# LB_BIT_o3_RGBLED-v02_rev1.net
KiCad netlist of a schematic drawn in EAGLE
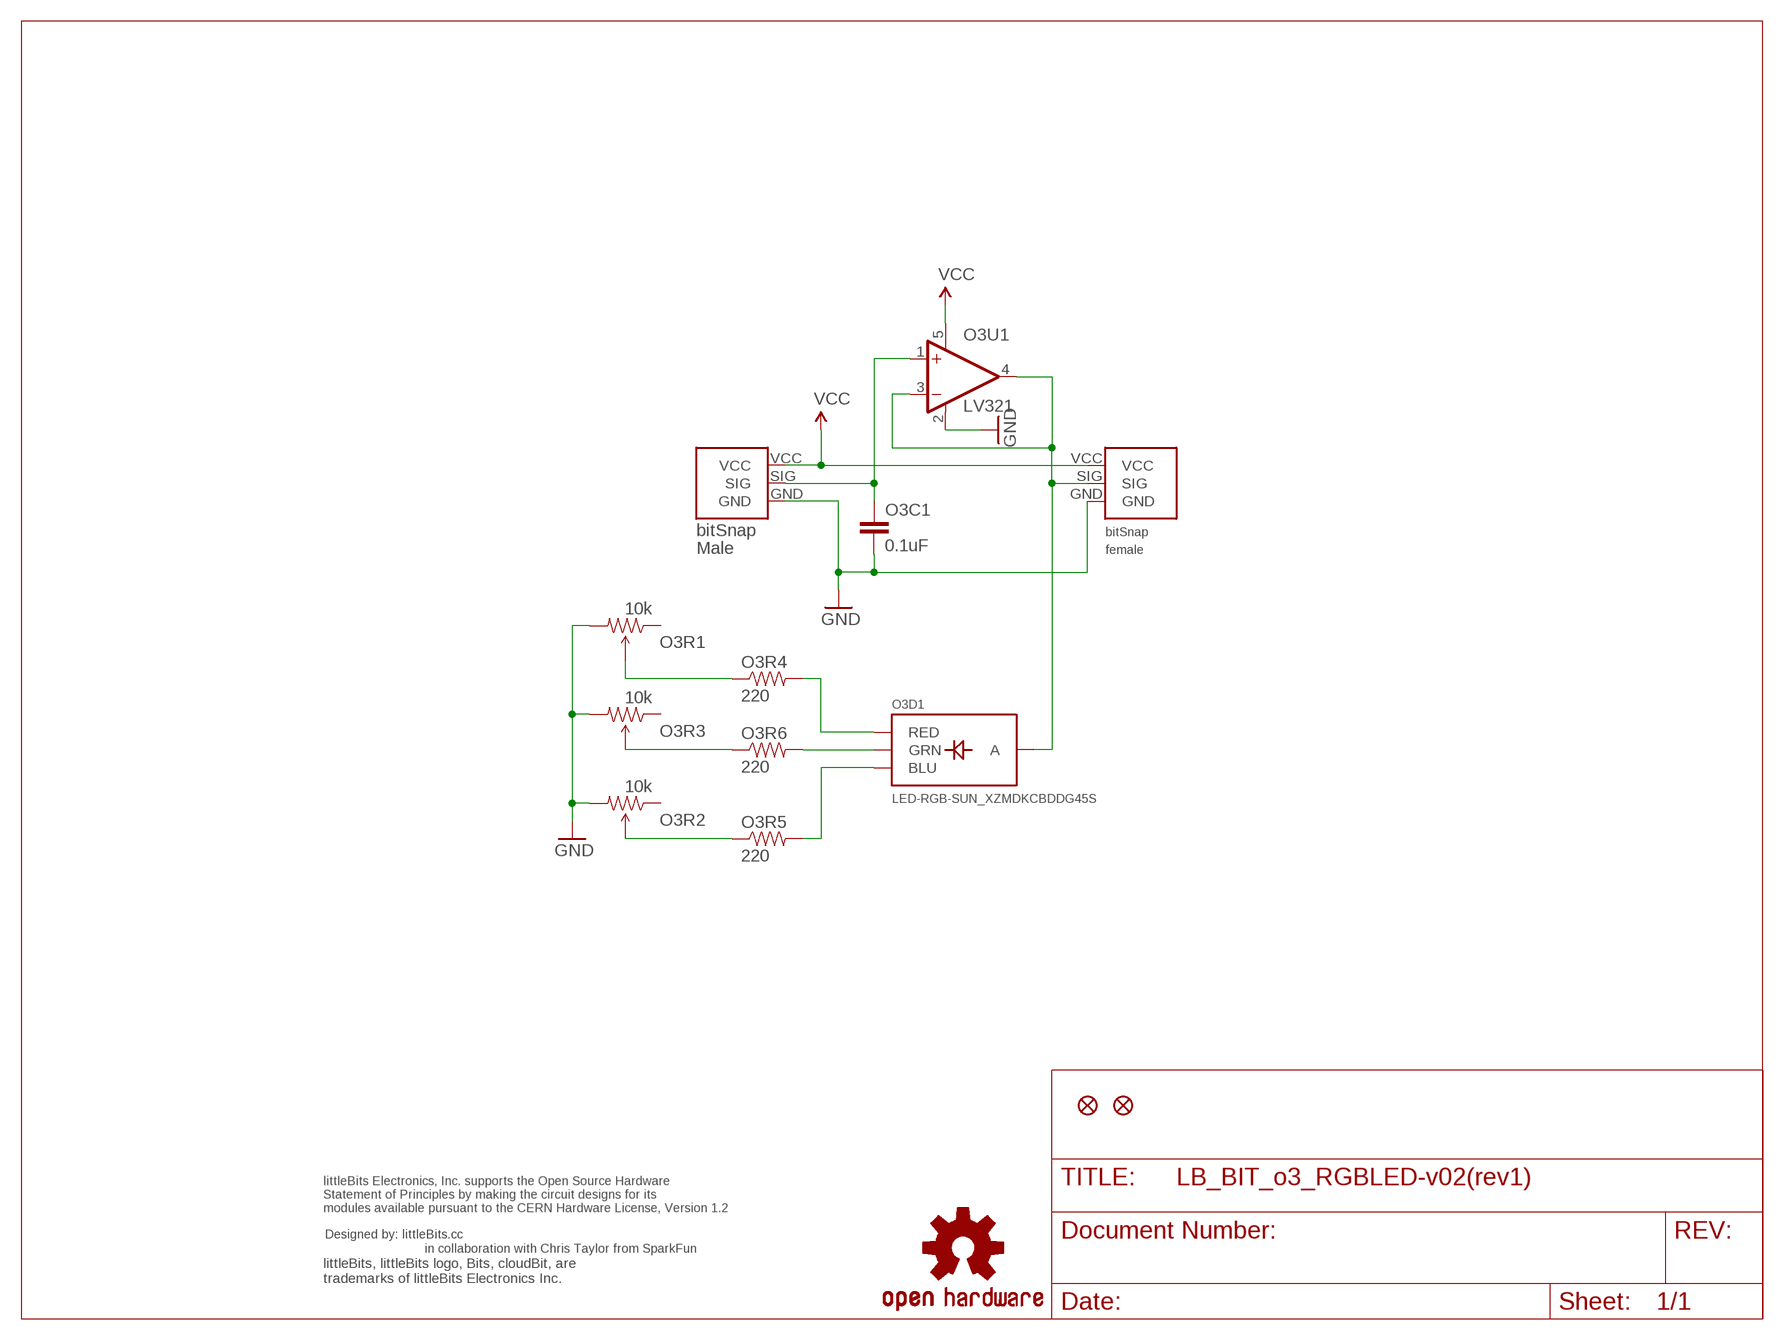
[diagram p0: schematic, sheet 1]

(export (version "E")
  (design (tool "Eeschema 10.0.6"))
  (components
    (comp (ref "JP1")
      (value "FIDUCIAL1X2.5")
      (footprint "eagle-import:FIDUCIAL-1X2.5")
      (libsource (lib "eagle-import") (part "FIDUCIAL1X2.5"))
    )
    (comp (ref "JP2")
      (value "FIDUCIAL1X2.5")
      (footprint "eagle-import:FIDUCIAL-1X2.5")
      (libsource (lib "eagle-import") (part "FIDUCIAL1X2.5"))
    )
    (comp (ref "O3BSF")
      (value "BITSNAP_FEMALE")
      (footprint "eagle-import:BITSNAP_FEMALE")
      (libsource (lib "eagle-import") (part "BITSNAP_FEMALE"))
    )
    (comp (ref "O3BSM")
      (value "BITSNAP_MALE")
      (footprint "eagle-import:BITSNAP_MALE")
      (libsource (lib "eagle-import") (part "BITSNAP_MALE"))
    )
    (comp (ref "O3C1")
      (value "0.1uF")
      (footprint "eagle-import:0603-CAP")
      (libsource (lib "eagle-import") (part "CAP0603-CAP"))
    )
    (comp (ref "O3D1")
      (value "LED-RGB-SUN_XZMDKCBDDG45S")
      (footprint "eagle-import:LED-RGB-SUN_XZMDKCBDDG45S")
      (libsource (lib "eagle-import") (part "LED-RGB-SUN_XZMDKCBDDG45S"))
    )
    (comp (ref "O3R1")
      (value "10k")
      (footprint "eagle-import:TRIMPOT-3MM")
      (libsource (lib "eagle-import") (part "TRIMPOTSMD"))
    )
    (comp (ref "O3R2")
      (value "10k")
      (footprint "eagle-import:TRIMPOT-3MM")
      (libsource (lib "eagle-import") (part "TRIMPOTSMD"))
    )
    (comp (ref "O3R3")
      (value "10k")
      (footprint "eagle-import:TRIMPOT-3MM")
      (libsource (lib "eagle-import") (part "TRIMPOTSMD"))
    )
    (comp (ref "O3R4")
      (value "220")
      (footprint "eagle-import:0603-RES")
      (libsource (lib "eagle-import") (part "RESISTOR0603-RES"))
    )
    (comp (ref "O3R5")
      (value "220")
      (footprint "eagle-import:0603-RES")
      (libsource (lib "eagle-import") (part "RESISTOR0603-RES"))
    )
    (comp (ref "O3R6")
      (value "220")
      (footprint "eagle-import:0603-RES")
      (libsource (lib "eagle-import") (part "RESISTOR0603-RES"))
    )
    (comp (ref "O3U1")
      (value "LV321")
      (footprint "eagle-import:SC70-5")
      (libsource (lib "eagle-import") (part "LV321"))
    )
    (comp (ref "U$1")
      (value "OSHWCREDIT")
      (footprint "eagle-import:OSHWCREDIT")
      (libsource (lib "eagle-import") (part "OSHWCREDIT"))
    )
    (comp (ref "U$5")
      (value "OSHW-LOGOL")
      (footprint "eagle-import:OSHW-LOGO-L")
      (libsource (lib "eagle-import") (part "OSHW-LOGOL"))
    )
  )
  (nets
    (net (code "1") (name "GND") (class "Default")
      (node (ref "O3BSF") (pin "GND") (pinfunction "GND_GND") (pintype "bidirectional"))
      (node (ref "O3BSM") (pin "GND") (pinfunction "GND_GND") (pintype "bidirectional"))
      (node (ref "O3C1") (pin "2") (pinfunction "2_2") (pintype "passive"))
      (node (ref "O3R1") (pin "3") (pinfunction "CW_3") (pintype "passive"))
      (node (ref "O3R2") (pin "3") (pinfunction "CW_3") (pintype "passive"))
      (node (ref "O3R3") (pin "3") (pinfunction "CW_3") (pintype "passive"))
      (node (ref "O3U1") (pin "2") (pinfunction "V-_2") (pintype "power_in"))
    )
    (net (code "2") (name "Net-(O3D1-A)") (class "Default")
      (node (ref "O3BSF") (pin "SIG") (pinfunction "SIG_SIG") (pintype "bidirectional"))
      (node (ref "O3D1") (pin "2") (pinfunction "A_2") (pintype "bidirectional"))
      (node (ref "O3U1") (pin "3") (pinfunction "-IN_3") (pintype "input"))
      (node (ref "O3U1") (pin "4") (pinfunction "OUT_4") (pintype "output"))
    )
    (net (code "3") (name "Net-(O3D1-BLU)") (class "Default")
      (node (ref "O3D1") (pin "3") (pinfunction "BLU_3") (pintype "bidirectional"))
      (node (ref "O3R5") (pin "2") (pinfunction "2_2") (pintype "passive"))
    )
    (net (code "4") (name "Net-(O3D1-GRN)") (class "Default")
      (node (ref "O3D1") (pin "4") (pinfunction "GRN_4") (pintype "bidirectional"))
      (node (ref "O3R6") (pin "2") (pinfunction "2_2") (pintype "passive"))
    )
    (net (code "5") (name "Net-(O3D1-RED)") (class "Default")
      (node (ref "O3D1") (pin "1") (pinfunction "RED_1") (pintype "bidirectional"))
      (node (ref "O3R4") (pin "2") (pinfunction "2_2") (pintype "passive"))
    )
    (net (code "6") (name "Net-(O3R1-WIPER)") (class "Default")
      (node (ref "O3R1") (pin "2") (pinfunction "WIPER_2") (pintype "passive"))
      (node (ref "O3R4") (pin "1") (pinfunction "1_1") (pintype "passive"))
    )
    (net (code "7") (name "Net-(O3R2-WIPER)") (class "Default")
      (node (ref "O3R2") (pin "2") (pinfunction "WIPER_2") (pintype "passive"))
      (node (ref "O3R5") (pin "1") (pinfunction "1_1") (pintype "passive"))
    )
    (net (code "8") (name "Net-(O3R3-WIPER)") (class "Default")
      (node (ref "O3R3") (pin "2") (pinfunction "WIPER_2") (pintype "passive"))
      (node (ref "O3R6") (pin "1") (pinfunction "1_1") (pintype "passive"))
    )
    (net (code "9") (name "Net-(O3U1-+IN)") (class "Default")
      (node (ref "O3BSM") (pin "SIG") (pinfunction "SIG_SIG") (pintype "bidirectional"))
      (node (ref "O3C1") (pin "1") (pinfunction "1_1") (pintype "passive"))
      (node (ref "O3U1") (pin "1") (pinfunction "+IN_1") (pintype "input"))
    )
    (net (code "10") (name "VCC") (class "Default")
      (node (ref "O3BSF") (pin "VCC") (pinfunction "VCC_VCC") (pintype "bidirectional"))
      (node (ref "O3BSM") (pin "VCC") (pinfunction "VCC_VCC") (pintype "bidirectional"))
      (node (ref "O3U1") (pin "5") (pinfunction "V+_5") (pintype "power_in"))
    )
    (net (code "11") (name "unconnected-(O3R1-CCW-Pad1)") (class "Default")
      (node (ref "O3R1") (pin "1") (pinfunction "CCW_1") (pintype "passive"))
    )
    (net (code "12") (name "unconnected-(O3R2-CCW-Pad1)") (class "Default")
      (node (ref "O3R2") (pin "1") (pinfunction "CCW_1") (pintype "passive"))
    )
    (net (code "13") (name "unconnected-(O3R3-CCW-Pad1)") (class "Default")
      (node (ref "O3R3") (pin "1") (pinfunction "CCW_1") (pintype "passive"))
    )
  )
)
